# SRB.net
KiCad netlist of a schematic drawn in EAGLE
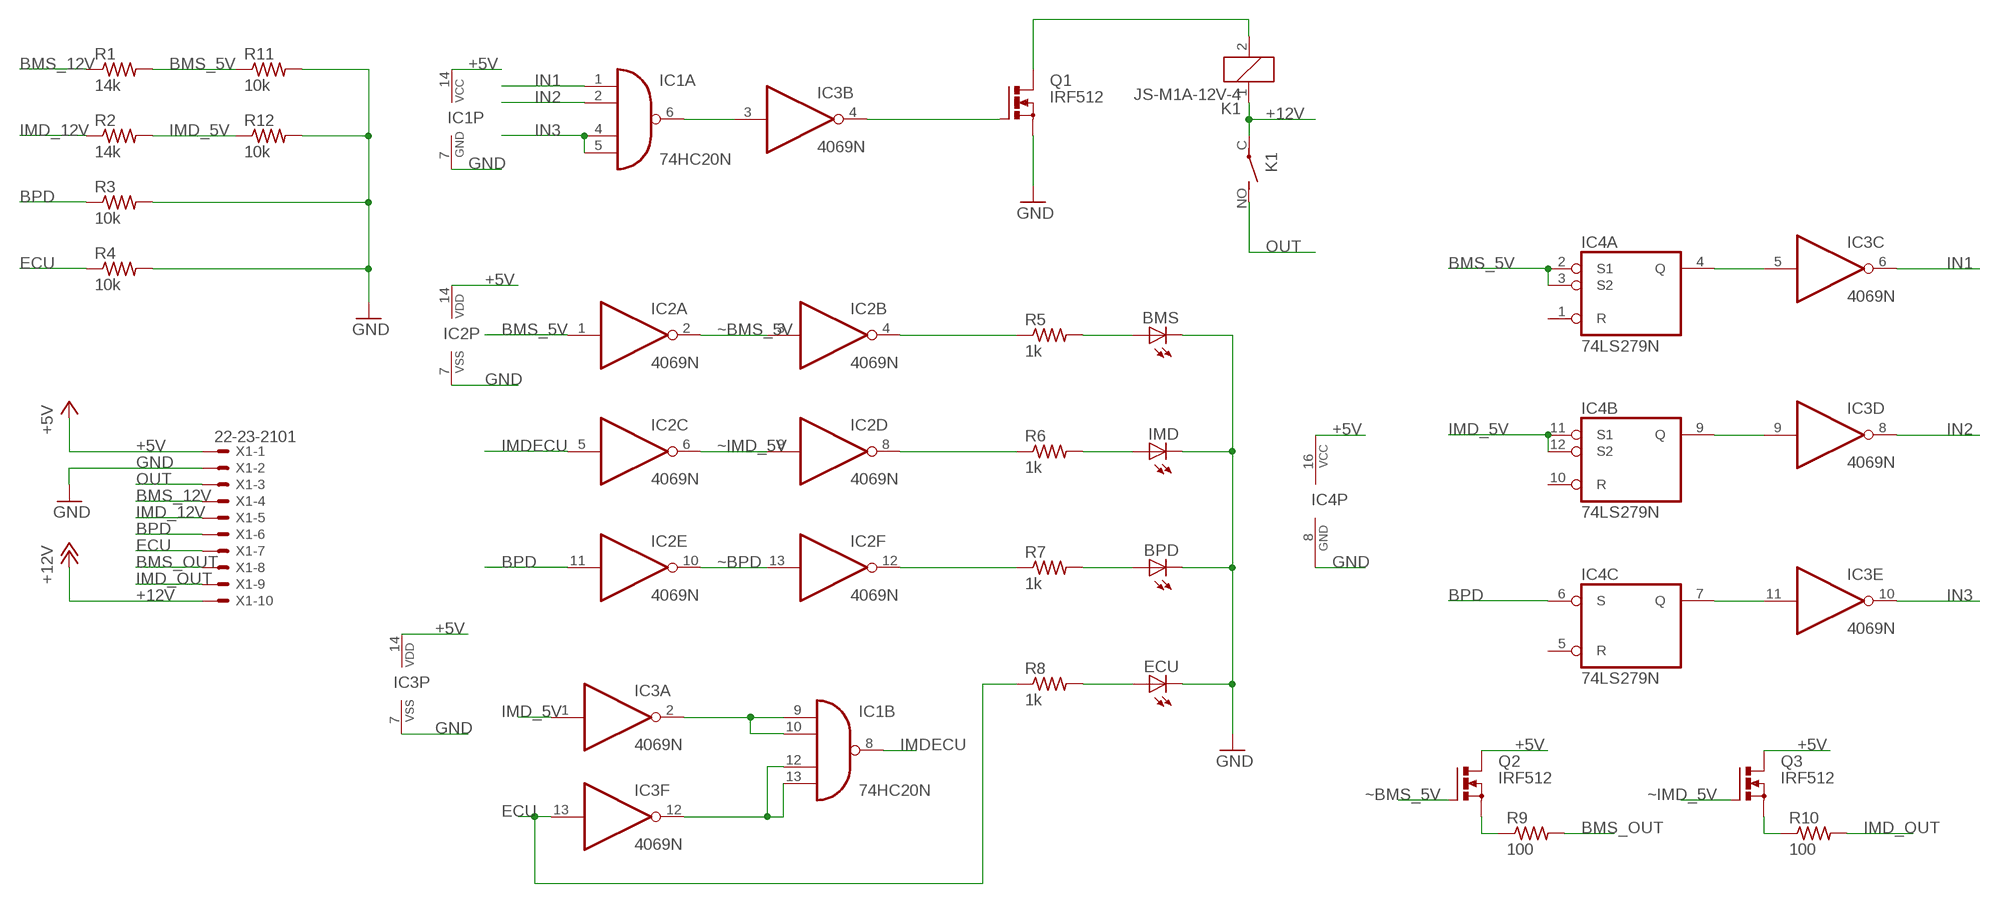
[diagram p0: schematic, sheet 1]

(export (version "E")
  (design (tool "Eeschema 10.0.6"))
  (components
    (comp (ref "BMS")
      (value "LED5MM")
      (footprint "eagle-import:LED5MM")
      (libsource (lib "eagle-import") (part "LED5MM"))
    )
    (comp (ref "BPD")
      (value "LED5MM")
      (footprint "eagle-import:LED5MM")
      (libsource (lib "eagle-import") (part "LED5MM"))
    )
    (comp (ref "ECU")
      (value "LED5MM")
      (footprint "eagle-import:LED5MM")
      (libsource (lib "eagle-import") (part "LED5MM"))
    )
    (comp (ref "IC1")
      (value "74HC20N")
      (footprint "eagle-import:DIL14")
      (libsource (lib "eagle-import") (part "7420NHC"))
    )
    (comp (ref "IC2")
      (value "4069N")
      (footprint "eagle-import:DIL14")
      (libsource (lib "eagle-import") (part "4069N"))
    )
    (comp (ref "IC3")
      (value "4069N")
      (footprint "eagle-import:DIL14")
      (libsource (lib "eagle-import") (part "4069N"))
    )
    (comp (ref "IC4")
      (value "74LS279N")
      (footprint "eagle-import:DIL16")
      (libsource (lib "eagle-import") (part "74279NLS"))
    )
    (comp (ref "IMD")
      (value "LED5MM")
      (footprint "eagle-import:LED5MM")
      (libsource (lib "eagle-import") (part "LED5MM"))
    )
    (comp (ref "K1")
      (value "JS-M1A-12V-4")
      (footprint "eagle-import:JS-M1A")
      (fields (field (name "MPN") "JSM1A-12V-4"))
      (libsource (lib "eagle-import") (part "JS-M1A-12V-4"))
    )
    (comp (ref "Q1")
      (value "IRF512")
      (footprint "eagle-import:TO220BV")
      (libsource (lib "eagle-import") (part "IRF512"))
    )
    (comp (ref "Q2")
      (value "IRF512")
      (footprint "eagle-import:TO220BV")
      (libsource (lib "eagle-import") (part "IRF512"))
    )
    (comp (ref "Q3")
      (value "IRF512")
      (footprint "eagle-import:TO220BV")
      (libsource (lib "eagle-import") (part "IRF512"))
    )
    (comp (ref "R1")
      (value "14k")
      (footprint "eagle-import:0207_10")
      (libsource (lib "eagle-import") (part "R-US_0207/10"))
    )
    (comp (ref "R2")
      (value "14k")
      (footprint "eagle-import:0207_10")
      (libsource (lib "eagle-import") (part "R-US_0207/10"))
    )
    (comp (ref "R3")
      (value "10k")
      (footprint "eagle-import:0207_10")
      (libsource (lib "eagle-import") (part "R-US_0207/10"))
    )
    (comp (ref "R4")
      (value "10k")
      (footprint "eagle-import:0207_10")
      (libsource (lib "eagle-import") (part "R-US_0207/10"))
    )
    (comp (ref "R5")
      (value "1k")
      (footprint "eagle-import:0207_10")
      (libsource (lib "eagle-import") (part "R-US_0207/10"))
    )
    (comp (ref "R6")
      (value "1k")
      (footprint "eagle-import:0207_10")
      (libsource (lib "eagle-import") (part "R-US_0207/10"))
    )
    (comp (ref "R7")
      (value "1k")
      (footprint "eagle-import:0207_10")
      (libsource (lib "eagle-import") (part "R-US_0207/10"))
    )
    (comp (ref "R8")
      (value "1k")
      (footprint "eagle-import:0207_10")
      (libsource (lib "eagle-import") (part "R-US_0207/10"))
    )
    (comp (ref "R9")
      (value "100")
      (footprint "eagle-import:0207_10")
      (libsource (lib "eagle-import") (part "R-US_0207/10"))
    )
    (comp (ref "R10")
      (value "100")
      (footprint "eagle-import:0207_10")
      (libsource (lib "eagle-import") (part "R-US_0207/10"))
    )
    (comp (ref "R11")
      (value "10k")
      (footprint "eagle-import:0207_10")
      (libsource (lib "eagle-import") (part "R-US_0207/10"))
    )
    (comp (ref "R12")
      (value "10k")
      (footprint "eagle-import:0207_10")
      (libsource (lib "eagle-import") (part "R-US_0207/10"))
    )
    (comp (ref "X1")
      (value "22-23-2101")
      (footprint "eagle-import:22-23-2101")
      (fields (field (name "MF") "MOLEX"))
      (libsource (lib "eagle-import") (part "22-23-2101"))
    )
  )
  (nets
    (net (code "1") (name "+5V") (class "Default")
      (node (ref "IC1") (pin "14") (pinfunction "VCC_14") (pintype "power_in"))
      (node (ref "IC2") (pin "14") (pinfunction "VDD_14") (pintype "power_in"))
      (node (ref "IC3") (pin "14") (pinfunction "VDD_14") (pintype "power_in"))
      (node (ref "IC4") (pin "16") (pinfunction "VCC_16") (pintype "power_in"))
      (node (ref "Q2") (pin "D") (pinfunction "D_D") (pintype "passive"))
      (node (ref "Q3") (pin "D") (pinfunction "D_D") (pintype "passive"))
      (node (ref "X1") (pin "1") (pinfunction "S_1") (pintype "passive"))
    )
    (net (code "2") (name "+12V") (class "Default")
      (node (ref "K1") (pin "1") (pinfunction "1_1") (pintype "passive"))
      (node (ref "K1") (pin "C") (pinfunction "P_C") (pintype "passive"))
      (node (ref "X1") (pin "10") (pinfunction "S_10") (pintype "passive"))
    )
    (net (code "3") (name "/BMS_5V") (class "Default")
      (node (ref "IC2") (pin "1") (pinfunction "I_1") (pintype "input"))
      (node (ref "IC4") (pin "2") (pinfunction "S1_2") (pintype "input"))
      (node (ref "IC4") (pin "3") (pinfunction "S2_3") (pintype "input"))
      (node (ref "R1") (pin "2") (pinfunction "2_2") (pintype "passive"))
      (node (ref "R11") (pin "1") (pinfunction "1_1") (pintype "passive"))
    )
    (net (code "4") (name "/BMS_12V") (class "Default")
      (node (ref "R1") (pin "1") (pinfunction "1_1") (pintype "passive"))
      (node (ref "X1") (pin "4") (pinfunction "S_4") (pintype "passive"))
    )
    (net (code "5") (name "/BMS_OUT") (class "Default")
      (node (ref "R9") (pin "2") (pinfunction "2_2") (pintype "passive"))
      (node (ref "X1") (pin "8") (pinfunction "S_8") (pintype "passive"))
    )
    (net (code "6") (name "/BPD") (class "Default")
      (node (ref "IC2") (pin "11") (pinfunction "I_11") (pintype "input"))
      (node (ref "IC4") (pin "6") (pinfunction "S_6") (pintype "input"))
      (node (ref "R3") (pin "1") (pinfunction "1_1") (pintype "passive"))
      (node (ref "X1") (pin "6") (pinfunction "S_6") (pintype "passive"))
    )
    (net (code "7") (name "/ECU") (class "Default")
      (node (ref "IC3") (pin "13") (pinfunction "I_13") (pintype "input"))
      (node (ref "R4") (pin "1") (pinfunction "1_1") (pintype "passive"))
      (node (ref "R8") (pin "1") (pinfunction "1_1") (pintype "passive"))
      (node (ref "X1") (pin "7") (pinfunction "S_7") (pintype "passive"))
    )
    (net (code "8") (name "/IMDECU") (class "Default")
      (node (ref "IC1") (pin "8") (pinfunction "O_8") (pintype "output"))
      (node (ref "IC2") (pin "5") (pinfunction "I_5") (pintype "input"))
    )
    (net (code "9") (name "/IMD_5V") (class "Default")
      (node (ref "IC3") (pin "1") (pinfunction "I_1") (pintype "input"))
      (node (ref "IC4") (pin "11") (pinfunction "S1_11") (pintype "input"))
      (node (ref "IC4") (pin "12") (pinfunction "S2_12") (pintype "input"))
      (node (ref "R12") (pin "1") (pinfunction "1_1") (pintype "passive"))
      (node (ref "R2") (pin "2") (pinfunction "2_2") (pintype "passive"))
    )
    (net (code "10") (name "/IMD_12V") (class "Default")
      (node (ref "R2") (pin "1") (pinfunction "1_1") (pintype "passive"))
      (node (ref "X1") (pin "5") (pinfunction "S_5") (pintype "passive"))
    )
    (net (code "11") (name "/IMD_OUT") (class "Default")
      (node (ref "R10") (pin "2") (pinfunction "2_2") (pintype "passive"))
      (node (ref "X1") (pin "9") (pinfunction "S_9") (pintype "passive"))
    )
    (net (code "12") (name "/IN1") (class "Default")
      (node (ref "IC1") (pin "1") (pinfunction "I0_1") (pintype "input"))
      (node (ref "IC3") (pin "6") (pinfunction "O_6") (pintype "output"))
    )
    (net (code "13") (name "/IN2") (class "Default")
      (node (ref "IC1") (pin "2") (pinfunction "I1_2") (pintype "input"))
      (node (ref "IC3") (pin "8") (pinfunction "O_8") (pintype "output"))
    )
    (net (code "14") (name "/IN3") (class "Default")
      (node (ref "IC1") (pin "4") (pinfunction "I2_4") (pintype "input"))
      (node (ref "IC1") (pin "5") (pinfunction "I3_5") (pintype "input"))
      (node (ref "IC3") (pin "10") (pinfunction "O_10") (pintype "output"))
    )
    (net (code "15") (name "/OUT") (class "Default")
      (node (ref "K1") (pin "NO") (pinfunction "S_NO") (pintype "passive"))
      (node (ref "X1") (pin "3") (pinfunction "S_3") (pintype "passive"))
    )
    (net (code "16") (name "/~{BMS_5V}") (class "Default")
      (node (ref "IC2") (pin "2") (pinfunction "O_2") (pintype "output"))
      (node (ref "IC2") (pin "3") (pinfunction "I_3") (pintype "input"))
      (node (ref "Q2") (pin "G") (pinfunction "G_G") (pintype "passive"))
    )
    (net (code "17") (name "/~{BPD}") (class "Default")
      (node (ref "IC2") (pin "10") (pinfunction "O_10") (pintype "output"))
      (node (ref "IC2") (pin "13") (pinfunction "I_13") (pintype "input"))
    )
    (net (code "18") (name "/~{IMD_5V}") (class "Default")
      (node (ref "IC2") (pin "6") (pinfunction "O_6") (pintype "output"))
      (node (ref "IC2") (pin "9") (pinfunction "I_9") (pintype "input"))
      (node (ref "Q3") (pin "G") (pinfunction "G_G") (pintype "passive"))
    )
    (net (code "19") (name "GND") (class "Default")
      (node (ref "BMS") (pin "K") (pinfunction "C_K") (pintype "passive"))
      (node (ref "BPD") (pin "K") (pinfunction "C_K") (pintype "passive"))
      (node (ref "ECU") (pin "K") (pinfunction "C_K") (pintype "passive"))
      (node (ref "IC1") (pin "7") (pinfunction "GND_7") (pintype "power_in"))
      (node (ref "IC2") (pin "7") (pinfunction "VSS_7") (pintype "power_in"))
      (node (ref "IC3") (pin "7") (pinfunction "VSS_7") (pintype "power_in"))
      (node (ref "IC4") (pin "8") (pinfunction "GND_8") (pintype "power_in"))
      (node (ref "IMD") (pin "K") (pinfunction "C_K") (pintype "passive"))
      (node (ref "Q1") (pin "S") (pinfunction "S_S") (pintype "passive"))
      (node (ref "R11") (pin "2") (pinfunction "2_2") (pintype "passive"))
      (node (ref "R12") (pin "2") (pinfunction "2_2") (pintype "passive"))
      (node (ref "R3") (pin "2") (pinfunction "2_2") (pintype "passive"))
      (node (ref "R4") (pin "2") (pinfunction "2_2") (pintype "passive"))
      (node (ref "X1") (pin "2") (pinfunction "S_2") (pintype "passive"))
    )
    (net (code "20") (name "Net-(BMS-PadA)") (class "Default")
      (node (ref "BMS") (pin "A") (pinfunction "A_A") (pintype "passive"))
      (node (ref "R5") (pin "2") (pinfunction "2_2") (pintype "passive"))
    )
    (net (code "21") (name "Net-(BPD-PadA)") (class "Default")
      (node (ref "BPD") (pin "A") (pinfunction "A_A") (pintype "passive"))
      (node (ref "R7") (pin "2") (pinfunction "2_2") (pintype "passive"))
    )
    (net (code "22") (name "Net-(ECU-PadA)") (class "Default")
      (node (ref "ECU") (pin "A") (pinfunction "A_A") (pintype "passive"))
      (node (ref "R8") (pin "2") (pinfunction "2_2") (pintype "passive"))
    )
    (net (code "23") (name "Net-(IC1A-O)") (class "Default")
      (node (ref "IC1") (pin "6") (pinfunction "O_6") (pintype "output"))
      (node (ref "IC3") (pin "3") (pinfunction "I_3") (pintype "input"))
    )
    (net (code "24") (name "Net-(IC1B-I0)") (class "Default")
      (node (ref "IC1") (pin "10") (pinfunction "I1_10") (pintype "input"))
      (node (ref "IC1") (pin "9") (pinfunction "I0_9") (pintype "input"))
      (node (ref "IC3") (pin "2") (pinfunction "O_2") (pintype "output"))
    )
    (net (code "25") (name "Net-(IC1B-I2)") (class "Default")
      (node (ref "IC1") (pin "12") (pinfunction "I2_12") (pintype "input"))
      (node (ref "IC1") (pin "13") (pinfunction "I3_13") (pintype "input"))
      (node (ref "IC3") (pin "12") (pinfunction "O_12") (pintype "output"))
    )
    (net (code "26") (name "Net-(IC2B-O)") (class "Default")
      (node (ref "IC2") (pin "4") (pinfunction "O_4") (pintype "output"))
      (node (ref "R5") (pin "1") (pinfunction "1_1") (pintype "passive"))
    )
    (net (code "27") (name "Net-(IC2D-O)") (class "Default")
      (node (ref "IC2") (pin "8") (pinfunction "O_8") (pintype "output"))
      (node (ref "R6") (pin "1") (pinfunction "1_1") (pintype "passive"))
    )
    (net (code "28") (name "Net-(IC2F-O)") (class "Default")
      (node (ref "IC2") (pin "12") (pinfunction "O_12") (pintype "output"))
      (node (ref "R7") (pin "1") (pinfunction "1_1") (pintype "passive"))
    )
    (net (code "29") (name "Net-(IC3B-O)") (class "Default")
      (node (ref "IC3") (pin "4") (pinfunction "O_4") (pintype "output"))
      (node (ref "Q1") (pin "G") (pinfunction "G_G") (pintype "passive"))
    )
    (net (code "30") (name "Net-(IC3C-I)") (class "Default")
      (node (ref "IC3") (pin "5") (pinfunction "I_5") (pintype "input"))
      (node (ref "IC4") (pin "4") (pinfunction "Q_4") (pintype "output"))
    )
    (net (code "31") (name "Net-(IC3D-I)") (class "Default")
      (node (ref "IC3") (pin "9") (pinfunction "I_9") (pintype "input"))
      (node (ref "IC4") (pin "9") (pinfunction "Q_9") (pintype "output"))
    )
    (net (code "32") (name "Net-(IC3E-I)") (class "Default")
      (node (ref "IC3") (pin "11") (pinfunction "I_11") (pintype "input"))
      (node (ref "IC4") (pin "7") (pinfunction "Q_7") (pintype "output"))
    )
    (net (code "33") (name "Net-(IMD-PadA)") (class "Default")
      (node (ref "IMD") (pin "A") (pinfunction "A_A") (pintype "passive"))
      (node (ref "R6") (pin "2") (pinfunction "2_2") (pintype "passive"))
    )
    (net (code "34") (name "Net-(K1-Pad2)") (class "Default")
      (node (ref "K1") (pin "2") (pinfunction "2_2") (pintype "passive"))
      (node (ref "Q1") (pin "D") (pinfunction "D_D") (pintype "passive"))
    )
    (net (code "35") (name "Net-(Q2-PadS)") (class "Default")
      (node (ref "Q2") (pin "S") (pinfunction "S_S") (pintype "passive"))
      (node (ref "R9") (pin "1") (pinfunction "1_1") (pintype "passive"))
    )
    (net (code "36") (name "Net-(Q3-PadS)") (class "Default")
      (node (ref "Q3") (pin "S") (pinfunction "S_S") (pintype "passive"))
      (node (ref "R10") (pin "1") (pinfunction "1_1") (pintype "passive"))
    )
    (net (code "37") (name "unconnected-(IC4A-R-Pad1)") (class "Default")
      (node (ref "IC4") (pin "1") (pinfunction "R_1") (pintype "input"))
    )
    (net (code "38") (name "unconnected-(IC4B-R-Pad10)") (class "Default")
      (node (ref "IC4") (pin "10") (pinfunction "R_10") (pintype "input"))
    )
    (net (code "39") (name "unconnected-(IC4C-R-Pad5)") (class "Default")
      (node (ref "IC4") (pin "5") (pinfunction "R_5") (pintype "input"))
    )
  )
)
